# CPU.net
KiCad netlist of a schematic drawn in Altium Designer
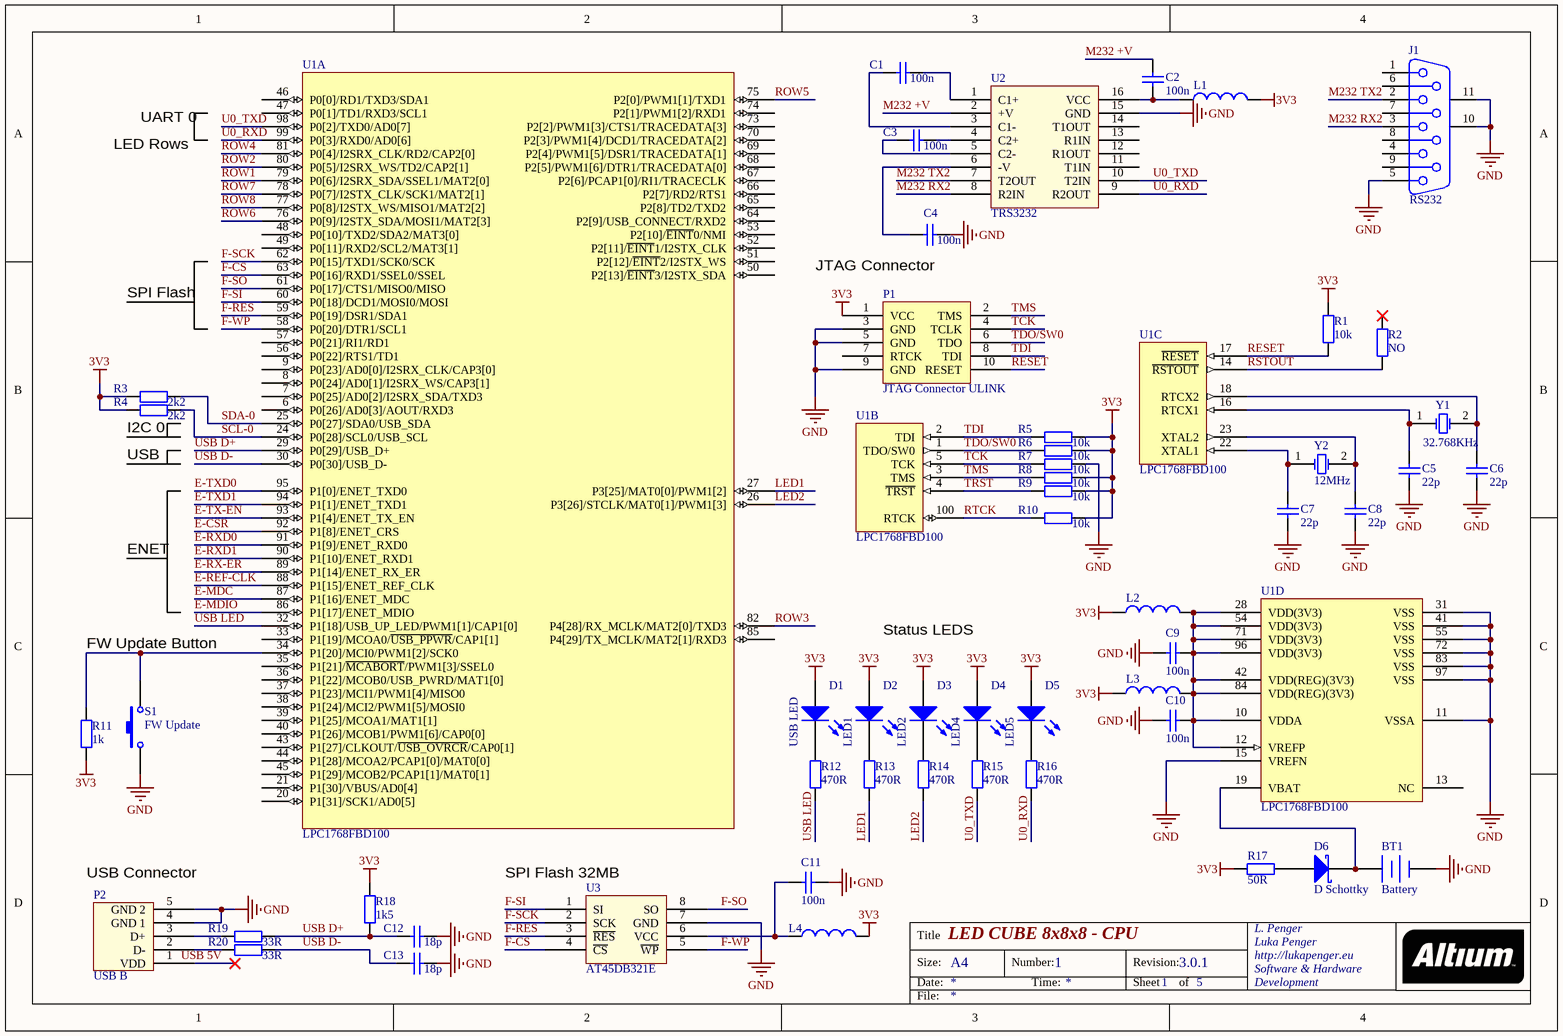
[diagram p0: CPU.SchDoc]

(export (version "E")
  (design (tool "Eeschema 10.0.6"))
  (components
    (comp (ref "BT1")
      (value "Battery")
      (footprint "Battery capacitor")
      (description "Multicell Battery")
      (fields (field (name "PUBLISHER") "Altium Limited"))
      (libsource (lib "Miscellaneous Devices") (part "Battery"))
    )
    (comp (ref "C1")
      (value "100n")
      (footprint "1608[0603]")
      (description "Capacitor")
      (fields (field (name "PUBLISHER") "Altium Limited"))
      (libsource (lib "Miscellaneous Devices") (part "Cap"))
    )
    (comp (ref "C2")
      (value "100n")
      (footprint "1608[0603]")
      (description "Capacitor")
      (fields (field (name "PUBLISHER") "Altium Limited"))
      (libsource (lib "Miscellaneous Devices") (part "Cap"))
    )
    (comp (ref "C3")
      (value "100n")
      (footprint "1608[0603]")
      (description "Capacitor")
      (fields (field (name "PUBLISHER") "Altium Limited"))
      (libsource (lib "Miscellaneous Devices") (part "Cap"))
    )
    (comp (ref "C4")
      (value "100n")
      (footprint "1608[0603]")
      (description "Capacitor")
      (fields (field (name "PUBLISHER") "Altium Limited"))
      (libsource (lib "Miscellaneous Devices") (part "Cap"))
    )
    (comp (ref "C5")
      (value "22p")
      (footprint "1608[0603]")
      (description "Capacitor")
      (fields (field (name "PUBLISHER") "Altium Limited"))
      (libsource (lib "Miscellaneous Devices") (part "Cap"))
    )
    (comp (ref "C6")
      (value "22p")
      (footprint "1608[0603]")
      (description "Capacitor")
      (fields (field (name "PUBLISHER") "Altium Limited"))
      (libsource (lib "Miscellaneous Devices") (part "Cap"))
    )
    (comp (ref "C7")
      (value "22p")
      (footprint "1608[0603]")
      (description "Capacitor")
      (fields (field (name "PUBLISHER") "Altium Limited"))
      (libsource (lib "Miscellaneous Devices") (part "Cap"))
    )
    (comp (ref "C8")
      (value "22p")
      (footprint "1608[0603]")
      (description "Capacitor")
      (fields (field (name "PUBLISHER") "Altium Limited"))
      (libsource (lib "Miscellaneous Devices") (part "Cap"))
    )
    (comp (ref "C9")
      (value "100n")
      (footprint "1608[0603]")
      (description "Capacitor")
      (fields (field (name "PUBLISHER") "Altium Limited"))
      (libsource (lib "Miscellaneous Devices") (part "Cap"))
    )
    (comp (ref "C10")
      (value "100n")
      (footprint "1608[0603]")
      (description "Capacitor")
      (fields (field (name "PUBLISHER") "Altium Limited"))
      (libsource (lib "Miscellaneous Devices") (part "Cap"))
    )
    (comp (ref "C11")
      (value "100n")
      (footprint "1608[0603]")
      (description "Capacitor")
      (fields (field (name "PUBLISHER") "Altium Limited"))
      (libsource (lib "Miscellaneous Devices") (part "Cap"))
    )
    (comp (ref "C12")
      (value "18p")
      (footprint "1608[0603]")
      (description "Capacitor")
      (fields (field (name "PUBLISHER") "Altium Limited"))
      (libsource (lib "Miscellaneous Devices") (part "Cap"))
    )
    (comp (ref "C13")
      (value "18p")
      (footprint "1608[0603]")
      (description "Capacitor")
      (fields (field (name "PUBLISHER") "Altium Limited"))
      (libsource (lib "Miscellaneous Devices") (part "Cap"))
    )
    (comp (ref "D1")
      (value "USB LED")
      (footprint "LED-1")
      (description "Typical INFRARED GaAs LED")
      (fields (field (name "PUBLISHER") "Altium Limited"))
      (libsource (lib "Miscellaneous Devices") (part "LED0"))
    )
    (comp (ref "D2")
      (value "LED1")
      (footprint "LED-1")
      (description "Typical INFRARED GaAs LED")
      (fields (field (name "PUBLISHER") "Altium Limited"))
      (libsource (lib "Miscellaneous Devices") (part "LED0"))
    )
    (comp (ref "D3")
      (value "LED2")
      (footprint "LED-1")
      (description "Typical INFRARED GaAs LED")
      (fields (field (name "PUBLISHER") "Altium Limited"))
      (libsource (lib "Miscellaneous Devices") (part "LED0"))
    )
    (comp (ref "D4")
      (value "LED4")
      (footprint "LED-1")
      (description "Typical INFRARED GaAs LED")
      (fields (field (name "PUBLISHER") "Altium Limited"))
      (libsource (lib "Miscellaneous Devices") (part "LED0"))
    )
    (comp (ref "D5")
      (value "LED5")
      (footprint "LED-1")
      (description "Typical INFRARED GaAs LED")
      (fields (field (name "PUBLISHER") "Altium Limited"))
      (libsource (lib "Miscellaneous Devices") (part "LED0"))
    )
    (comp (ref "D6")
      (value "D Schottky")
      (footprint "SMB")
      (description "Schottky Diode")
      (fields (field (name "PUBLISHER") "Altium Limited"))
      (libsource (lib "Miscellaneous Devices") (part "D Schottky"))
    )
    (comp (ref "J1")
      (value "RS232")
      (footprint "DSUB1.385-2H9")
      (description "Receptacle Assembly, 9 Position, Right Angle")
      (fields (field (name "PUBLISHER") "Altium Limited"))
      (libsource (lib "Miscellaneous Connectors") (part "D Connector 9"))
    )
    (comp (ref "L1")
      (value "Inductor")
      (footprint "1608[0603]")
      (fields (field (name "PUBLISHER") "Altium Limited"))
      (libsource (lib "Miscellaneous Devices") (part "Inductor"))
    )
    (comp (ref "L2")
      (value "Inductor")
      (footprint "1608[0603]")
      (fields (field (name "PUBLISHER") "Altium Limited"))
      (libsource (lib "Miscellaneous Devices") (part "Inductor"))
    )
    (comp (ref "L3")
      (value "Inductor")
      (footprint "1608[0603]")
      (fields (field (name "PUBLISHER") "Altium Limited"))
      (libsource (lib "Miscellaneous Devices") (part "Inductor"))
    )
    (comp (ref "L4")
      (value "Inductor")
      (footprint "1608[0603]")
      (fields (field (name "PUBLISHER") "Altium Limited"))
      (libsource (lib "Miscellaneous Devices") (part "Inductor"))
    )
    (comp (ref "P1")
      (value "JTAG Connector ULINK")
      (footprint "JTAG Connector ULINK")
      (description "JTAG Connector")
      (libsource (lib "LP_Lib") (part "JTAG Connector ULINK"))
    )
    (comp (ref "P2")
      (value "USB B")
      (footprint "USB B")
      (description "USB Connector")
      (libsource (lib "LP_Lib") (part "USB B"))
    )
    (comp (ref "R1")
      (value "10k")
      (footprint "1608[0603]")
      (description "Resistor")
      (fields (field (name "PUBLISHER") "Altium Limited"))
      (libsource (lib "Miscellaneous Devices") (part "Res2"))
    )
    (comp (ref "R2")
      (value "NO")
      (footprint "1608[0603]")
      (description "Resistor")
      (fields (field (name "PUBLISHER") "Altium Limited"))
      (libsource (lib "Miscellaneous Devices") (part "Res2"))
    )
    (comp (ref "R3")
      (value "2k2")
      (footprint "1608[0603]")
      (description "Resistor")
      (fields (field (name "PUBLISHER") "Altium Limited"))
      (libsource (lib "") (part "Res2_1"))
    )
    (comp (ref "R4")
      (value "2k2")
      (footprint "1608[0603]")
      (description "Resistor")
      (fields (field (name "PUBLISHER") "Altium Limited"))
      (libsource (lib "") (part "Res2_1"))
    )
    (comp (ref "R5")
      (value "10k")
      (footprint "1608[0603]")
      (description "Resistor")
      (fields (field (name "PUBLISHER") "Altium Limited"))
      (libsource (lib "") (part "Res2_1"))
    )
    (comp (ref "R6")
      (value "10k")
      (footprint "1608[0603]")
      (description "Resistor")
      (fields (field (name "PUBLISHER") "Altium Limited"))
      (libsource (lib "") (part "Res2_1"))
    )
    (comp (ref "R7")
      (value "10k")
      (footprint "1608[0603]")
      (description "Resistor")
      (fields (field (name "PUBLISHER") "Altium Limited"))
      (libsource (lib "") (part "Res2_1"))
    )
    (comp (ref "R8")
      (value "10k")
      (footprint "1608[0603]")
      (description "Resistor")
      (fields (field (name "PUBLISHER") "Altium Limited"))
      (libsource (lib "") (part "Res2_1"))
    )
    (comp (ref "R9")
      (value "10k")
      (footprint "1608[0603]")
      (description "Resistor")
      (fields (field (name "PUBLISHER") "Altium Limited"))
      (libsource (lib "") (part "Res2_1"))
    )
    (comp (ref "R10")
      (value "10k")
      (footprint "1608[0603]")
      (description "Resistor")
      (fields (field (name "PUBLISHER") "Altium Limited"))
      (libsource (lib "") (part "Res2_1"))
    )
    (comp (ref "R11")
      (value "1k")
      (footprint "1608[0603]")
      (description "Resistor")
      (fields (field (name "PUBLISHER") "Altium Limited"))
      (libsource (lib "Miscellaneous Devices") (part "Res2"))
    )
    (comp (ref "R12")
      (value "470R")
      (footprint "1608[0603]")
      (description "Resistor")
      (fields (field (name "PUBLISHER") "Altium Limited"))
      (libsource (lib "Miscellaneous Devices") (part "Res2"))
    )
    (comp (ref "R13")
      (value "470R")
      (footprint "1608[0603]")
      (description "Resistor")
      (fields (field (name "PUBLISHER") "Altium Limited"))
      (libsource (lib "Miscellaneous Devices") (part "Res2"))
    )
    (comp (ref "R14")
      (value "470R")
      (footprint "1608[0603]")
      (description "Resistor")
      (fields (field (name "PUBLISHER") "Altium Limited"))
      (libsource (lib "Miscellaneous Devices") (part "Res2"))
    )
    (comp (ref "R15")
      (value "470R")
      (footprint "1608[0603]")
      (description "Resistor")
      (fields (field (name "PUBLISHER") "Altium Limited"))
      (libsource (lib "Miscellaneous Devices") (part "Res2"))
    )
    (comp (ref "R16")
      (value "470R")
      (footprint "1608[0603]")
      (description "Resistor")
      (fields (field (name "PUBLISHER") "Altium Limited"))
      (libsource (lib "Miscellaneous Devices") (part "Res2"))
    )
    (comp (ref "R17")
      (value "50R")
      (footprint "6-0805_N")
      (description "Resistor")
      (fields (field (name "PUBLISHER") "Altium Limited"))
      (libsource (lib "") (part "Res2_2"))
    )
    (comp (ref "R18")
      (value "1k5")
      (footprint "1608[0603]")
      (description "Resistor")
      (fields (field (name "PUBLISHER") "Altium Limited"))
      (libsource (lib "") (part "Res2_3"))
    )
    (comp (ref "R19")
      (value "33R")
      (footprint "1608[0603]")
      (description "Resistor")
      (fields (field (name "PUBLISHER") "Altium Limited"))
      (libsource (lib "") (part "Res2_2"))
    )
    (comp (ref "R20")
      (value "33R")
      (footprint "1608[0603]")
      (description "Resistor")
      (fields (field (name "PUBLISHER") "Altium Limited"))
      (libsource (lib "") (part "Res2_2"))
    )
    (comp (ref "S1")
      (value "FW Update")
      (footprint "SWITCH-TACTILE-90")
      (description "Switch")
      (fields (field (name "PUBLISHER") "Altium Limited"))
      (libsource (lib "Miscellaneous Devices") (part "SW-PB"))
    )
    (comp (ref "U1")
      (value "LPC1768FBD100")
      (footprint "SOT407-1_N")
      (fields (field (name "PUBLISHER") "Altium Limited"))
      (libsource (lib "") (part "LPC1768FBD100_1"))
    )
    (comp (ref "U2")
      (value "TRS3232")
      (footprint "SOIC16_N")
      (description "Dual 232 +3V3")
      (libsource (lib "LP_Lib") (part "MAX2232"))
    )
    (comp (ref "U3")
      (value "AT45DB321E")
      (footprint "AT45DB321D")
      (description "SPI Flash 32MB")
      (libsource (lib "LP_Lib") (part "AT45DB321D"))
    )
    (comp (ref "Y1")
      (value "32.768KHz")
      (footprint "Crystal 4.1x1.5")
      (description "Crystal Oscillator")
      (fields (field (name "PUBLISHER") "Altium Limited"))
      (libsource (lib "Miscellaneous Devices") (part "XTAL"))
    )
    (comp (ref "Y2")
      (value "12MHz")
      (footprint "5x3.2 Crystal")
      (description "Crystal Oscillator")
      (fields (field (name "PUBLISHER") "Altium Limited"))
      (libsource (lib "Miscellaneous Devices") (part "XTAL"))
    )
  )
  (nets
    (net (code "1") (name "/E-CSR") (class "Default")
      (node (ref "U1") (pin "92") (pinfunction "P1[8]/ENET_CRS_92") (pintype "bidirectional"))
    )
    (net (code "2") (name "/E-MDC") (class "Default")
      (node (ref "U1") (pin "87") (pinfunction "P1[16]/ENET_MDC_87") (pintype "bidirectional"))
    )
    (net (code "3") (name "/E-MDIO") (class "Default")
      (node (ref "U1") (pin "86") (pinfunction "P1[17]/ENET_MDIO_86") (pintype "bidirectional"))
    )
    (net (code "4") (name "/E-REF-CLK") (class "Default")
      (node (ref "U1") (pin "88") (pinfunction "P1[15]/ENET_REF_CLK_88") (pintype "bidirectional"))
    )
    (net (code "5") (name "/E-RX-ER") (class "Default")
      (node (ref "U1") (pin "89") (pinfunction "P1[14]/ENET_RX_ER_89") (pintype "bidirectional"))
    )
    (net (code "6") (name "/E-RXD0") (class "Default")
      (node (ref "U1") (pin "91") (pinfunction "P1[9]/ENET_RXD0_91") (pintype "bidirectional"))
    )
    (net (code "7") (name "/E-RXD1") (class "Default")
      (node (ref "U1") (pin "90") (pinfunction "P1[10]/ENET_RXD1_90") (pintype "bidirectional"))
    )
    (net (code "8") (name "/E-TX-EN") (class "Default")
      (node (ref "U1") (pin "93") (pinfunction "P1[4]/ENET_TX_EN_93") (pintype "bidirectional"))
    )
    (net (code "9") (name "/E-TXD0") (class "Default")
      (node (ref "U1") (pin "95") (pinfunction "P1[0]/ENET_TXD0_95") (pintype "bidirectional"))
    )
    (net (code "10") (name "/E-TXD1") (class "Default")
      (node (ref "U1") (pin "94") (pinfunction "P1[1]/ENET_TXD1_94") (pintype "bidirectional"))
    )
    (net (code "11") (name "/F-CS") (class "Default")
      (node (ref "U1") (pin "63") (pinfunction "P0[16]/RXD1/SSEL0/SSEL_63") (pintype "bidirectional"))
      (node (ref "U3") (pin "4") (pinfunction "~{CS}_4") (pintype "passive"))
    )
    (net (code "12") (name "/F-RES") (class "Default")
      (node (ref "U1") (pin "59") (pinfunction "P0[19]/DSR1/SDA1_59") (pintype "bidirectional"))
      (node (ref "U3") (pin "3") (pinfunction "~{RES}_3") (pintype "passive"))
    )
    (net (code "13") (name "/F-SCK") (class "Default")
      (node (ref "U1") (pin "62") (pinfunction "P0[15]/TXD1/SCK0/SCK_62") (pintype "bidirectional"))
      (node (ref "U3") (pin "2") (pinfunction "SCK_2") (pintype "passive"))
    )
    (net (code "14") (name "/F-SI") (class "Default")
      (node (ref "U1") (pin "60") (pinfunction "P0[18]/DCD1/MOSI0/MOSI_60") (pintype "bidirectional"))
      (node (ref "U3") (pin "1") (pinfunction "SI_1") (pintype "passive"))
    )
    (net (code "15") (name "/F-SO") (class "Default")
      (node (ref "U1") (pin "61") (pinfunction "P0[17]/CTS1/MISO0/MISO_61") (pintype "bidirectional"))
      (node (ref "U3") (pin "8") (pinfunction "SO_8") (pintype "passive"))
    )
    (net (code "16") (name "/F-WP") (class "Default")
      (node (ref "U1") (pin "58") (pinfunction "P0[20]/DTR1/SCL1_58") (pintype "bidirectional"))
      (node (ref "U3") (pin "5") (pinfunction "~{WP}_5") (pintype "passive"))
    )
    (net (code "17") (name "/LED1") (class "Default")
      (node (ref "R13") (pin "1") (pinfunction "1_1") (pintype "passive"))
      (node (ref "U1") (pin "27") (pinfunction "P3[25]/MAT0[0]/PWM1[2]_27") (pintype "bidirectional"))
    )
    (net (code "18") (name "/LED2") (class "Default")
      (node (ref "R14") (pin "1") (pinfunction "1_1") (pintype "passive"))
      (node (ref "U1") (pin "26") (pinfunction "P3[26]/STCLK/MAT0[1]/PWM1[3]_26") (pintype "bidirectional"))
    )
    (net (code "19") (name "/M232 +V") (class "Default")
      (node (ref "C2") (pin "1") (pinfunction "1_1") (pintype "passive"))
      (node (ref "U2") (pin "2") (pinfunction "+V_2") (pintype "passive"))
    )
    (net (code "20") (name "/M232 RX2") (class "Default")
      (node (ref "J1") (pin "3") (pinfunction "3_3") (pintype "passive"))
      (node (ref "U2") (pin "8") (pinfunction "R2IN_8") (pintype "passive"))
    )
    (net (code "21") (name "/M232 TX2") (class "Default")
      (node (ref "J1") (pin "2") (pinfunction "2_2") (pintype "passive"))
      (node (ref "U2") (pin "7") (pinfunction "T2OUT_7") (pintype "passive"))
    )
    (net (code "22") (name "/RESET") (class "Default")
      (node (ref "P1") (pin "10") (pinfunction "RESET_10") (pintype "passive"))
      (node (ref "R1") (pin "1") (pinfunction "1_1") (pintype "passive"))
      (node (ref "U1") (pin "17") (pinfunction "~{RESET}_17") (pintype "input"))
    )
    (net (code "23") (name "/ROW1") (class "Default")
      (node (ref "U1") (pin "79") (pinfunction "P0[6]/I2SRX_SDA/SSEL1/MAT2[0]_79") (pintype "bidirectional"))
    )
    (net (code "24") (name "/ROW2") (class "Default")
      (node (ref "U1") (pin "80") (pinfunction "P0[5]/I2SRX_WS/TD2/CAP2[1]_80") (pintype "bidirectional"))
    )
    (net (code "25") (name "/ROW3") (class "Default")
      (node (ref "U1") (pin "82") (pinfunction "P4[28]/RX_MCLK/MAT2[0]/TXD3_82") (pintype "bidirectional"))
    )
    (net (code "26") (name "/ROW4") (class "Default")
      (node (ref "U1") (pin "81") (pinfunction "P0[4]/I2SRX_CLK/RD2/CAP2[0]_81") (pintype "bidirectional"))
    )
    (net (code "27") (name "/ROW5") (class "Default")
      (node (ref "U1") (pin "75") (pinfunction "P2[0]/PWM1[1]/TXD1_75") (pintype "bidirectional"))
    )
    (net (code "28") (name "/ROW6") (class "Default")
      (node (ref "U1") (pin "76") (pinfunction "P0[9]/I2STX_SDA/MOSI1/MAT2[3]_76") (pintype "bidirectional"))
    )
    (net (code "29") (name "/ROW7") (class "Default")
      (node (ref "U1") (pin "78") (pinfunction "P0[7]/I2STX_CLK/SCK1/MAT2[1]_78") (pintype "bidirectional"))
    )
    (net (code "30") (name "/ROW8") (class "Default")
      (node (ref "U1") (pin "77") (pinfunction "P0[8]/I2STX_WS/MISO1/MAT2[2]_77") (pintype "bidirectional"))
    )
    (net (code "31") (name "/RSTOUT") (class "Default")
      (node (ref "R2") (pin "1") (pinfunction "1_1") (pintype "passive"))
      (node (ref "U1") (pin "14") (pinfunction "~{RSTOUT}_14") (pintype "output"))
    )
    (net (code "32") (name "/RTCK") (class "Default")
      (node (ref "R10") (pin "1") (pinfunction "1_1") (pintype "passive"))
      (node (ref "U1") (pin "100") (pinfunction "RTCK_100") (pintype "bidirectional"))
    )
    (net (code "33") (name "/SCL-0") (class "Default")
      (node (ref "R4") (pin "2") (pinfunction "2_2") (pintype "passive"))
      (node (ref "U1") (pin "24") (pinfunction "P0[28]/SCL0/USB_SCL_24") (pintype "bidirectional"))
    )
    (net (code "34") (name "/SDA-0") (class "Default")
      (node (ref "R3") (pin "2") (pinfunction "2_2") (pintype "passive"))
      (node (ref "U1") (pin "25") (pinfunction "P0[27]/SDA0/USB_SDA_25") (pintype "bidirectional"))
    )
    (net (code "35") (name "/TCK") (class "Default")
      (node (ref "P1") (pin "4") (pinfunction "TCLK_4") (pintype "passive"))
      (node (ref "R7") (pin "1") (pinfunction "1_1") (pintype "passive"))
      (node (ref "U1") (pin "5") (pinfunction "TCK_5") (pintype "input"))
    )
    (net (code "36") (name "/TDI") (class "Default")
      (node (ref "P1") (pin "8") (pinfunction "TDI_8") (pintype "passive"))
      (node (ref "R5") (pin "1") (pinfunction "1_1") (pintype "passive"))
      (node (ref "U1") (pin "2") (pinfunction "TDI_2") (pintype "input"))
    )
    (net (code "37") (name "/TDO{slash}SW0") (class "Default")
      (node (ref "P1") (pin "6") (pinfunction "TDO_6") (pintype "passive"))
      (node (ref "R6") (pin "1") (pinfunction "1_1") (pintype "passive"))
      (node (ref "U1") (pin "1") (pinfunction "TDO/SW0_1") (pintype "output"))
    )
    (net (code "38") (name "/TMS") (class "Default")
      (node (ref "P1") (pin "2") (pinfunction "TMS_2") (pintype "passive"))
      (node (ref "R8") (pin "1") (pinfunction "1_1") (pintype "passive"))
      (node (ref "U1") (pin "3") (pinfunction "TMS_3") (pintype "input"))
    )
    (net (code "39") (name "/TRST") (class "Default")
      (node (ref "R9") (pin "1") (pinfunction "1_1") (pintype "passive"))
      (node (ref "U1") (pin "4") (pinfunction "~{TRST}_4") (pintype "input"))
    )
    (net (code "40") (name "/U0_RXD") (class "Default")
      (node (ref "R16") (pin "1") (pinfunction "1_1") (pintype "passive"))
      (node (ref "U1") (pin "99") (pinfunction "P0[3]/RXD0/AD0[6]_99") (pintype "bidirectional"))
      (node (ref "U2") (pin "9") (pinfunction "R2OUT_9") (pintype "passive"))
    )
    (net (code "41") (name "/U0_TXD") (class "Default")
      (node (ref "R15") (pin "1") (pinfunction "1_1") (pintype "passive"))
      (node (ref "U1") (pin "98") (pinfunction "P0[2]/TXD0/AD0[7]_98") (pintype "bidirectional"))
      (node (ref "U2") (pin "10") (pinfunction "T2IN_10") (pintype "passive"))
    )
    (net (code "43") (name "/USB D+") (class "Default")
      (node (ref "C12") (pin "1") (pinfunction "1_1") (pintype "passive"))
      (node (ref "R18") (pin "2") (pinfunction "2_2") (pintype "passive"))
      (node (ref "R19") (pin "1") (pinfunction "1_1") (pintype "passive"))
      (node (ref "U1") (pin "29") (pinfunction "P0[29]/USB_D+_29") (pintype "bidirectional"))
    )
    (net (code "44") (name "/USB D-") (class "Default")
      (node (ref "C13") (pin "1") (pinfunction "1_1") (pintype "passive"))
      (node (ref "R20") (pin "1") (pinfunction "1_1") (pintype "passive"))
      (node (ref "U1") (pin "30") (pinfunction "P0[30]/USB_D-_30") (pintype "bidirectional"))
    )
    (net (code "45") (name "/USB LED") (class "Default")
      (node (ref "R12") (pin "1") (pinfunction "1_1") (pintype "passive"))
      (node (ref "U1") (pin "32") (pinfunction "P1[18]/USB_UP_LED/PWM1[1]/CAP1[0]_32") (pintype "bidirectional"))
    )
    (net (code "46") (name "3V3") (class "Default")
      (node (ref "D1") (pin "1") (pinfunction "A_1") (pintype "passive"))
      (node (ref "D2") (pin "1") (pinfunction "A_1") (pintype "passive"))
      (node (ref "D3") (pin "1") (pinfunction "A_1") (pintype "passive"))
      (node (ref "D4") (pin "1") (pinfunction "A_1") (pintype "passive"))
      (node (ref "D5") (pin "1") (pinfunction "A_1") (pintype "passive"))
      (node (ref "L1") (pin "2") (pinfunction "2_2") (pintype "passive"))
      (node (ref "L2") (pin "1") (pinfunction "1_1") (pintype "passive"))
      (node (ref "L3") (pin "1") (pinfunction "1_1") (pintype "passive"))
      (node (ref "L4") (pin "2") (pinfunction "2_2") (pintype "passive"))
      (node (ref "P1") (pin "1") (pinfunction "VCC_1") (pintype "passive"))
      (node (ref "R1") (pin "2") (pinfunction "2_2") (pintype "passive"))
      (node (ref "R10") (pin "2") (pinfunction "2_2") (pintype "passive"))
      (node (ref "R11") (pin "1") (pinfunction "1_1") (pintype "passive"))
      (node (ref "R17") (pin "2") (pinfunction "2_2") (pintype "passive"))
      (node (ref "R18") (pin "1") (pinfunction "1_1") (pintype "passive"))
      (node (ref "R3") (pin "1") (pinfunction "1_1") (pintype "passive"))
      (node (ref "R4") (pin "1") (pinfunction "1_1") (pintype "passive"))
      (node (ref "R5") (pin "2") (pinfunction "2_2") (pintype "passive"))
      (node (ref "R6") (pin "2") (pinfunction "2_2") (pintype "passive"))
      (node (ref "R8") (pin "2") (pinfunction "2_2") (pintype "passive"))
      (node (ref "R9") (pin "2") (pinfunction "2_2") (pintype "passive"))
    )
    (net (code "47") (name "GND") (class "Default")
      (node (ref "BT1") (pin "2") (pinfunction "-_2") (pintype "passive"))
      (node (ref "C10") (pin "1") (pinfunction "1_1") (pintype "passive"))
      (node (ref "C11") (pin "1") (pinfunction "1_1") (pintype "passive"))
      (node (ref "C12") (pin "2") (pinfunction "2_2") (pintype "passive"))
      (node (ref "C13") (pin "2") (pinfunction "2_2") (pintype "passive"))
      (node (ref "C4") (pin "1") (pinfunction "1_1") (pintype "passive"))
      (node (ref "C5") (pin "1") (pinfunction "1_1") (pintype "passive"))
      (node (ref "C6") (pin "1") (pinfunction "1_1") (pintype "passive"))
      (node (ref "C7") (pin "1") (pinfunction "1_1") (pintype "passive"))
      (node (ref "C8") (pin "1") (pinfunction "1_1") (pintype "passive"))
      (node (ref "C9") (pin "2") (pinfunction "2_2") (pintype "passive"))
      (node (ref "J1") (pin "10") (pinfunction "MH1_10") (pintype "passive"))
      (node (ref "J1") (pin "11") (pinfunction "MH2_11") (pintype "passive"))
      (node (ref "J1") (pin "5") (pinfunction "5_5") (pintype "passive"))
      (node (ref "P1") (pin "3") (pinfunction "GND_3") (pintype "passive"))
      (node (ref "P1") (pin "5") (pinfunction "GND_5") (pintype "passive"))
      (node (ref "P1") (pin "9") (pinfunction "GND_9") (pintype "passive"))
      (node (ref "P2") (pin "4") (pinfunction "GND_1_4") (pintype "passive"))
      (node (ref "P2") (pin "5") (pinfunction "GND_2_5") (pintype "passive"))
      (node (ref "R7") (pin "2") (pinfunction "2_2") (pintype "passive"))
      (node (ref "S1") (pin "1") (pinfunction "1_1") (pintype "passive"))
      (node (ref "U1") (pin "11") (pinfunction "VSSA_11") (pintype "power_in"))
      (node (ref "U1") (pin "15") (pinfunction "VREFN_15") (pintype "power_in"))
      (node (ref "U1") (pin "31") (pinfunction "VSS_31") (pintype "power_in"))
      (node (ref "U1") (pin "41") (pinfunction "VSS_41") (pintype "power_in"))
      (node (ref "U1") (pin "55") (pinfunction "VSS_55") (pintype "power_in"))
      (node (ref "U1") (pin "72") (pinfunction "VSS_72") (pintype "power_in"))
      (node (ref "U1") (pin "83") (pinfunction "VSS_83") (pintype "power_in"))
      (node (ref "U1") (pin "97") (pinfunction "VSS_97") (pintype "power_in"))
      (node (ref "U2") (pin "15") (pinfunction "GND_15") (pintype "passive"))
      (node (ref "U3") (pin "7") (pinfunction "GND_7") (pintype "passive"))
    )
    (net (code "48") (name "Net-(BT1-+)") (class "Default")
      (node (ref "BT1") (pin "1") (pinfunction "+_1") (pintype "passive"))
      (node (ref "D6") (pin "2") (pinfunction "K_2") (pintype "passive"))
      (node (ref "U1") (pin "19") (pinfunction "VBAT_19") (pintype "power_in"))
    )
    (net (code "49") (name "Net-(D1-K)") (class "Default")
      (node (ref "D1") (pin "2") (pinfunction "K_2") (pintype "passive"))
      (node (ref "R12") (pin "2") (pinfunction "2_2") (pintype "passive"))
    )
    (net (code "50") (name "Net-(D2-K)") (class "Default")
      (node (ref "D2") (pin "2") (pinfunction "K_2") (pintype "passive"))
      (node (ref "R13") (pin "2") (pinfunction "2_2") (pintype "passive"))
    )
    (net (code "51") (name "Net-(D3-K)") (class "Default")
      (node (ref "D3") (pin "2") (pinfunction "K_2") (pintype "passive"))
      (node (ref "R14") (pin "2") (pinfunction "2_2") (pintype "passive"))
    )
    (net (code "52") (name "Net-(D4-K)") (class "Default")
      (node (ref "D4") (pin "2") (pinfunction "K_2") (pintype "passive"))
      (node (ref "R15") (pin "2") (pinfunction "2_2") (pintype "passive"))
    )
    (net (code "53") (name "Net-(D5-K)") (class "Default")
      (node (ref "D5") (pin "2") (pinfunction "K_2") (pintype "passive"))
      (node (ref "R16") (pin "2") (pinfunction "2_2") (pintype "passive"))
    )
    (net (code "54") (name "Net-(D6-A)") (class "Default")
      (node (ref "D6") (pin "1") (pinfunction "A_1") (pintype "passive"))
      (node (ref "R17") (pin "1") (pinfunction "1_1") (pintype "passive"))
    )
    (net (code "55") (name "Net-(P2-D+)") (class "Default")
      (node (ref "P2") (pin "3") (pinfunction "D+_3") (pintype "passive"))
      (node (ref "R19") (pin "2") (pinfunction "2_2") (pintype "passive"))
    )
    (net (code "56") (name "Net-(P2-D-)") (class "Default")
      (node (ref "P2") (pin "2") (pinfunction "D-_2") (pintype "passive"))
      (node (ref "R20") (pin "2") (pinfunction "2_2") (pintype "passive"))
    )
    (net (code "57") (name "Net-(U1A-P1[20]{slash}MCI0{slash}PWM1[2]{slash}SCK0)") (class "Default")
      (node (ref "R11") (pin "2") (pinfunction "2_2") (pintype "passive"))
      (node (ref "S1") (pin "2") (pinfunction "2_2") (pintype "passive"))
      (node (ref "U1") (pin "34") (pinfunction "P1[20]/MCI0/PWM1[2]/SCK0_34") (pintype "bidirectional"))
    )
    (net (code "58") (name "Net-(U1C-RTCX1)") (class "Default")
      (node (ref "C5") (pin "2") (pinfunction "2_2") (pintype "passive"))
      (node (ref "U1") (pin "16") (pinfunction "RTCX1_16") (pintype "input"))
      (node (ref "Y1") (pin "1") (pinfunction "OSC1_1") (pintype "passive"))
    )
    (net (code "59") (name "Net-(U1C-RTCX2)") (class "Default")
      (node (ref "C6") (pin "2") (pinfunction "2_2") (pintype "passive"))
      (node (ref "U1") (pin "18") (pinfunction "RTCX2_18") (pintype "output"))
      (node (ref "Y1") (pin "2") (pinfunction "OSC2_2") (pintype "passive"))
    )
    (net (code "60") (name "Net-(U1C-XTAL1)") (class "Default")
      (node (ref "C7") (pin "2") (pinfunction "2_2") (pintype "passive"))
      (node (ref "U1") (pin "22") (pinfunction "XTAL1_22") (pintype "input"))
      (node (ref "Y2") (pin "1") (pinfunction "OSC1_1") (pintype "passive"))
    )
    (net (code "61") (name "Net-(U1C-XTAL2)") (class "Default")
      (node (ref "C8") (pin "2") (pinfunction "2_2") (pintype "passive"))
      (node (ref "U1") (pin "23") (pinfunction "XTAL2_23") (pintype "output"))
      (node (ref "Y2") (pin "2") (pinfunction "OSC2_2") (pintype "passive"))
    )
    (net (code "62") (name "Net-(U1D-VDDA)") (class "Default")
      (node (ref "C10") (pin "2") (pinfunction "2_2") (pintype "passive"))
      (node (ref "C9") (pin "1") (pinfunction "1_1") (pintype "passive"))
      (node (ref "L2") (pin "2") (pinfunction "2_2") (pintype "passive"))
      (node (ref "L3") (pin "2") (pinfunction "2_2") (pintype "passive"))
      (node (ref "U1") (pin "10") (pinfunction "VDDA_10") (pintype "power_in"))
      (node (ref "U1") (pin "12") (pinfunction "VREFP_12") (pintype "input"))
      (node (ref "U1") (pin "28") (pinfunction "VDD(3V3)_28") (pintype "power_in"))
      (node (ref "U1") (pin "42") (pinfunction "VDD(REG)(3V3)_42") (pintype "power_in"))
      (node (ref "U1") (pin "54") (pinfunction "VDD(3V3)_54") (pintype "power_in"))
      (node (ref "U1") (pin "71") (pinfunction "VDD(3V3)_71") (pintype "power_in"))
      (node (ref "U1") (pin "84") (pinfunction "VDD(REG)(3V3)_84") (pintype "power_in"))
      (node (ref "U1") (pin "96") (pinfunction "VDD(3V3)_96") (pintype "power_in"))
    )
    (net (code "63") (name "Net-(U2--V)") (class "Default")
      (node (ref "C4") (pin "2") (pinfunction "2_2") (pintype "passive"))
      (node (ref "U2") (pin "6") (pinfunction "-V_6") (pintype "passive"))
    )
    (net (code "64") (name "Net-(U2-C1+)") (class "Default")
      (node (ref "C1") (pin "2") (pinfunction "2_2") (pintype "passive"))
      (node (ref "U2") (pin "1") (pinfunction "C1+_1") (pintype "passive"))
    )
    (net (code "65") (name "Net-(U2-C1-)") (class "Default")
      (node (ref "C1") (pin "1") (pinfunction "1_1") (pintype "passive"))
      (node (ref "U2") (pin "3") (pinfunction "C1-_3") (pintype "passive"))
    )
    (net (code "66") (name "Net-(U2-C2+)") (class "Default")
      (node (ref "C3") (pin "2") (pinfunction "2_2") (pintype "passive"))
      (node (ref "U2") (pin "4") (pinfunction "C2+_4") (pintype "passive"))
    )
    (net (code "67") (name "Net-(U2-C2-)") (class "Default")
      (node (ref "C3") (pin "1") (pinfunction "1_1") (pintype "passive"))
      (node (ref "U2") (pin "5") (pinfunction "C2-_5") (pintype "passive"))
    )
    (net (code "68") (name "Net-(U2-VCC)") (class "Default")
      (node (ref "C2") (pin "2") (pinfunction "2_2") (pintype "passive"))
      (node (ref "L1") (pin "1") (pinfunction "1_1") (pintype "passive"))
      (node (ref "U2") (pin "16") (pinfunction "VCC_16") (pintype "passive"))
    )
    (net (code "69") (name "Net-(U3-VCC)") (class "Default")
      (node (ref "C11") (pin "2") (pinfunction "2_2") (pintype "passive"))
      (node (ref "L4") (pin "1") (pinfunction "1_1") (pintype "passive"))
      (node (ref "U3") (pin "6") (pinfunction "VCC_6") (pintype "passive"))
    )
    (net (code "70") (name "unconnected-(J1-Pad1)") (class "Default")
      (node (ref "J1") (pin "1") (pinfunction "1_1") (pintype "passive"))
    )
    (net (code "71") (name "unconnected-(J1-Pad4)") (class "Default")
      (node (ref "J1") (pin "4") (pinfunction "4_4") (pintype "passive"))
    )
    (net (code "72") (name "unconnected-(J1-Pad6)") (class "Default")
      (node (ref "J1") (pin "6") (pinfunction "6_6") (pintype "passive"))
    )
    (net (code "73") (name "unconnected-(J1-Pad7)") (class "Default")
      (node (ref "J1") (pin "7") (pinfunction "7_7") (pintype "passive"))
    )
    (net (code "74") (name "unconnected-(J1-Pad8)") (class "Default")
      (node (ref "J1") (pin "8") (pinfunction "8_8") (pintype "passive"))
    )
    (net (code "75") (name "unconnected-(J1-Pad9)") (class "Default")
      (node (ref "J1") (pin "9") (pinfunction "9_9") (pintype "passive"))
    )
    (net (code "76") (name "unconnected-(P1-RTCK-Pad7)") (class "Default")
      (node (ref "P1") (pin "7") (pinfunction "RTCK_7") (pintype "passive"))
    )
    (net (code "77") (name "unconnected-(P2-VDD-Pad1)") (class "Default")
      (node (ref "P2") (pin "1") (pinfunction "VDD_1") (pintype "passive+no_connect"))
    )
    (net (code "78") (name "unconnected-(R2-Pad2)") (class "Default")
      (node (ref "R2") (pin "2") (pinfunction "2_2") (pintype "passive+no_connect"))
    )
    (net (code "79") (name "unconnected-(U1A-P0[0]{slash}RD1{slash}TXD3{slash}SDA1-Pad46)") (class "Default")
      (node (ref "U1") (pin "46") (pinfunction "P0[0]/RD1/TXD3/SDA1_46") (pintype "bidirectional"))
    )
    (net (code "80") (name "unconnected-(U1A-P0[1]{slash}TD1{slash}RXD3{slash}SCL1-Pad47)") (class "Default")
      (node (ref "U1") (pin "47") (pinfunction "P0[1]/TD1/RXD3/SCL1_47") (pintype "bidirectional"))
    )
    (net (code "81") (name "unconnected-(U1A-P0[10]{slash}TXD2{slash}SDA2{slash}MAT3[0]-Pad48)") (class "Default")
      (node (ref "U1") (pin "48") (pinfunction "P0[10]/TXD2/SDA2/MAT3[0]_48") (pintype "bidirectional"))
    )
    (net (code "82") (name "unconnected-(U1A-P0[11]{slash}RXD2{slash}SCL2{slash}MAT3[1]-Pad49)") (class "Default")
      (node (ref "U1") (pin "49") (pinfunction "P0[11]/RXD2/SCL2/MAT3[1]_49") (pintype "bidirectional"))
    )
    (net (code "83") (name "unconnected-(U1A-P0[21]{slash}RI1{slash}RD1-Pad57)") (class "Default")
      (node (ref "U1") (pin "57") (pinfunction "P0[21]/RI1/RD1_57") (pintype "bidirectional"))
    )
    (net (code "84") (name "unconnected-(U1A-P0[22]{slash}RTS1{slash}TD1-Pad56)") (class "Default")
      (node (ref "U1") (pin "56") (pinfunction "P0[22]/RTS1/TD1_56") (pintype "bidirectional"))
    )
    (net (code "85") (name "unconnected-(U1A-P0[23]{slash}AD0[0]{slash}I2SRX_CLK{slash}CAP3[0]-Pad9)") (class "Default")
      (node (ref "U1") (pin "9") (pinfunction "P0[23]/AD0[0]/I2SRX_CLK/CAP3[0]_9") (pintype "bidirectional"))
    )
    (net (code "86") (name "unconnected-(U1A-P0[24]{slash}AD0[1]{slash}I2SRX_WS{slash}CAP3[1]-Pad8)") (class "Default")
      (node (ref "U1") (pin "8") (pinfunction "P0[24]/AD0[1]/I2SRX_WS/CAP3[1]_8") (pintype "bidirectional"))
    )
    (net (code "87") (name "unconnected-(U1A-P0[25]{slash}AD0[2]{slash}I2SRX_SDA{slash}TXD3-Pad7)") (class "Default")
      (node (ref "U1") (pin "7") (pinfunction "P0[25]/AD0[2]/I2SRX_SDA/TXD3_7") (pintype "bidirectional"))
    )
    (net (code "88") (name "unconnected-(U1A-P0[26]{slash}AD0[3]{slash}AOUT{slash}RXD3-Pad6)") (class "Default")
      (node (ref "U1") (pin "6") (pinfunction "P0[26]/AD0[3]/AOUT/RXD3_6") (pintype "bidirectional"))
    )
    (net (code "89") (name "unconnected-(U1A-P1[19]{slash}MCOA0{slash}~{USB_PPWR}{slash}CAP1[1]-Pad33)") (class "Default")
      (node (ref "U1") (pin "33") (pinfunction "P1[19]/MCOA0/~{USB_PPWR}/CAP1[1]_33") (pintype "bidirectional"))
    )
    (net (code "90") (name "unconnected-(U1A-P1[21]{slash}~{MCABORT}{slash}PWM1[3]{slash}SSEL0-Pad35)") (class "Default")
      (node (ref "U1") (pin "35") (pinfunction "P1[21]/~{MCABORT}/PWM1[3]/SSEL0_35") (pintype "bidirectional"))
    )
    (net (code "91") (name "unconnected-(U1A-P1[22]{slash}MCOB0{slash}USB_PWRD{slash}MAT1[0]-Pad36)") (class "Default")
      (node (ref "U1") (pin "36") (pinfunction "P1[22]/MCOB0/USB_PWRD/MAT1[0]_36") (pintype "bidirectional"))
    )
    (net (code "92") (name "unconnected-(U1A-P1[23]{slash}MCI1{slash}PWM1[4]{slash}MISO0-Pad37)") (class "Default")
      (node (ref "U1") (pin "37") (pinfunction "P1[23]/MCI1/PWM1[4]/MISO0_37") (pintype "bidirectional"))
    )
    (net (code "93") (name "unconnected-(U1A-P1[24]{slash}MCI2{slash}PWM1[5]{slash}MOSI0-Pad38)") (class "Default")
      (node (ref "U1") (pin "38") (pinfunction "P1[24]/MCI2/PWM1[5]/MOSI0_38") (pintype "bidirectional"))
    )
    (net (code "94") (name "unconnected-(U1A-P1[25]{slash}MCOA1{slash}MAT1[1]-Pad39)") (class "Default")
      (node (ref "U1") (pin "39") (pinfunction "P1[25]/MCOA1/MAT1[1]_39") (pintype "bidirectional"))
    )
    (net (code "95") (name "unconnected-(U1A-P1[26]{slash}MCOB1{slash}PWM1[6]{slash}CAP0[0]-Pad40)") (class "Default")
      (node (ref "U1") (pin "40") (pinfunction "P1[26]/MCOB1/PWM1[6]/CAP0[0]_40") (pintype "bidirectional"))
    )
    (net (code "96") (name "unconnected-(U1A-P1[27]{slash}CLKOUT{slash}~{USB_OVRCR}{slash}CAP0[1]-Pad43)") (class "Default")
      (node (ref "U1") (pin "43") (pinfunction "P1[27]/CLKOUT/~{USB_OVRCR}/CAP0[1]_43") (pintype "bidirectional"))
    )
    (net (code "97") (name "unconnected-(U1A-P1[28]{slash}MCOA2{slash}PCAP1[0]{slash}MAT0[0]-Pad44)") (class "Default")
      (node (ref "U1") (pin "44") (pinfunction "P1[28]/MCOA2/PCAP1[0]/MAT0[0]_44") (pintype "bidirectional"))
    )
    (net (code "98") (name "unconnected-(U1A-P1[29]{slash}MCOB2{slash}PCAP1[1]{slash}MAT0[1]-Pad45)") (class "Default")
      (node (ref "U1") (pin "45") (pinfunction "P1[29]/MCOB2/PCAP1[1]/MAT0[1]_45") (pintype "bidirectional"))
    )
    (net (code "99") (name "unconnected-(U1A-P1[30]{slash}VBUS{slash}AD0[4]-Pad21)") (class "Default")
      (node (ref "U1") (pin "21") (pinfunction "P1[30]/VBUS/AD0[4]_21") (pintype "bidirectional"))
    )
    (net (code "100") (name "unconnected-(U1A-P1[31]{slash}SCK1{slash}AD0[5]-Pad20)") (class "Default")
      (node (ref "U1") (pin "20") (pinfunction "P1[31]/SCK1/AD0[5]_20") (pintype "bidirectional"))
    )
    (net (code "101") (name "unconnected-(U1A-P2[1]{slash}PWM1[2]{slash}RXD1-Pad74)") (class "Default")
      (node (ref "U1") (pin "74") (pinfunction "P2[1]/PWM1[2]/RXD1_74") (pintype "bidirectional"))
    )
    (net (code "102") (name "unconnected-(U1A-P2[2]{slash}PWM1[3]{slash}CTS1{slash}TRACEDATA[3]-Pad73)") (class "Default")
      (node (ref "U1") (pin "73") (pinfunction "P2[2]/PWM1[3]/CTS1/TRACEDATA[3]_73") (pintype "bidirectional"))
    )
    (net (code "103") (name "unconnected-(U1A-P2[3]{slash}PWM1[4]{slash}DCD1{slash}TRACEDATA[2]-Pad70)") (class "Default")
      (node (ref "U1") (pin "70") (pinfunction "P2[3]/PWM1[4]/DCD1/TRACEDATA[2]_70") (pintype "bidirectional"))
    )
    (net (code "104") (name "unconnected-(U1A-P2[4]{slash}PWM1[5]{slash}DSR1{slash}TRACEDATA[1]-Pad69)") (class "Default")
      (node (ref "U1") (pin "69") (pinfunction "P2[4]/PWM1[5]/DSR1/TRACEDATA[1]_69") (pintype "bidirectional"))
    )
    (net (code "105") (name "unconnected-(U1A-P2[5]{slash}PWM1[6]{slash}DTR1{slash}TRACEDATA[0]-Pad68)") (class "Default")
      (node (ref "U1") (pin "68") (pinfunction "P2[5]/PWM1[6]/DTR1/TRACEDATA[0]_68") (pintype "bidirectional"))
    )
    (net (code "106") (name "unconnected-(U1A-P2[6]{slash}PCAP1[0]{slash}RI1{slash}TRACECLK-Pad67)") (class "Default")
      (node (ref "U1") (pin "67") (pinfunction "P2[6]/PCAP1[0]/RI1/TRACECLK_67") (pintype "bidirectional"))
    )
    (net (code "107") (name "unconnected-(U1A-P2[7]{slash}RD2{slash}RTS1-Pad66)") (class "Default")
      (node (ref "U1") (pin "66") (pinfunction "P2[7]/RD2/RTS1_66") (pintype "bidirectional"))
    )
    (net (code "108") (name "unconnected-(U1A-P2[8]{slash}TD2{slash}TXD2-Pad65)") (class "Default")
      (node (ref "U1") (pin "65") (pinfunction "P2[8]/TD2/TXD2_65") (pintype "bidirectional"))
    )
    (net (code "109") (name "unconnected-(U1A-P2[9]{slash}USB_CONNECT{slash}RXD2-Pad64)") (class "Default")
      (node (ref "U1") (pin "64") (pinfunction "P2[9]/USB_CONNECT/RXD2_64") (pintype "bidirectional"))
    )
    (net (code "110") (name "unconnected-(U1A-P2[10]{slash}~{EINT}0{slash}NMI-Pad53)") (class "Default")
      (node (ref "U1") (pin "53") (pinfunction "P2[10]/~{EINT}0/NMI_53") (pintype "bidirectional"))
    )
    (net (code "111") (name "unconnected-(U1A-P2[11]{slash}~{EINT}1{slash}I2STX_CLK-Pad52)") (class "Default")
      (node (ref "U1") (pin "52") (pinfunction "P2[11]/~{EINT}1/I2STX_CLK_52") (pintype "bidirectional"))
    )
    (net (code "112") (name "unconnected-(U1A-P2[12]{slash}~{EINT}2{slash}I2STX_WS-Pad51)") (class "Default")
      (node (ref "U1") (pin "51") (pinfunction "P2[12]/~{EINT}2/I2STX_WS_51") (pintype "bidirectional"))
    )
    (net (code "113") (name "unconnected-(U1A-P2[13]{slash}~{EINT}3{slash}I2STX_SDA-Pad50)") (class "Default")
      (node (ref "U1") (pin "50") (pinfunction "P2[13]/~{EINT}3/I2STX_SDA_50") (pintype "bidirectional"))
    )
    (net (code "114") (name "unconnected-(U1A-P4[29]{slash}TX_MCLK{slash}MAT2[1]{slash}RXD3-Pad85)") (class "Default")
      (node (ref "U1") (pin "85") (pinfunction "P4[29]/TX_MCLK/MAT2[1]/RXD3_85") (pintype "bidirectional"))
    )
    (net (code "115") (name "unconnected-(U1D-NC-Pad13)") (class "Default")
      (node (ref "U1") (pin "13") (pinfunction "NC_13") (pintype "power_in"))
    )
    (net (code "116") (name "unconnected-(U2-R1IN-Pad13)") (class "Default")
      (node (ref "U2") (pin "13") (pinfunction "R1IN_13") (pintype "passive"))
    )
    (net (code "117") (name "unconnected-(U2-R1OUT-Pad12)") (class "Default")
      (node (ref "U2") (pin "12") (pinfunction "R1OUT_12") (pintype "passive"))
    )
    (net (code "118") (name "unconnected-(U2-T1IN-Pad11)") (class "Default")
      (node (ref "U2") (pin "11") (pinfunction "T1IN_11") (pintype "passive"))
    )
    (net (code "119") (name "unconnected-(U2-T1OUT-Pad14)") (class "Default")
      (node (ref "U2") (pin "14") (pinfunction "T1OUT_14") (pintype "passive"))
    )
  )
)
